# boost.net
KiCad netlist of a schematic drawn in Altium Designer
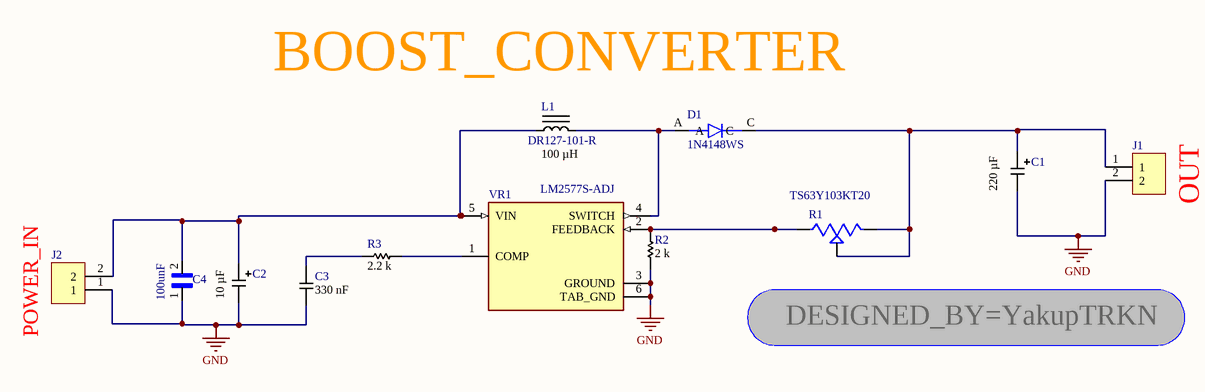
[diagram p0: boost__.SchDoc]

(export (version "E")
  (design (tool "Eeschema 10.0.6"))
  (components
    (comp (ref "C1")
      (value "TAJC227M010RNJ")
      (footprint "KYOCERA_CAP_TAN-C")
      (description "CAP TANT 220UF 20% 10V 2312")
      (fields (field (name "CAPACITANCE") "220 µF"))
      (libsource (lib "boost") (part "TAJC227M010RNJ"))
    )
    (comp (ref "C2")
      (value "T491B106M016AT")
      (footprint "KEMET_CAP_TAN-B")
      (description "CAP TANT 10UF 20% 16V 1411")
      (fields (field (name "CAPACITANCE") "10 µF"))
      (libsource (lib "boost") (part "T491B106M016AT"))
    )
    (comp (ref "C3")
      (value "CL21B334KOCNNNC")
      (footprint "SAMSUNG_CAP_0805_095")
      (description "CAP CER 0.33UF 16V X7R 0805")
      (fields (field (name "CAPACITANCE") "330 nF"))
      (libsource (lib "boost") (part "CL21B334KOCNNNC"))
    )
    (comp (ref "C4")
      (value "100unF")
      (footprint "VJ0603Y104KLXAC5G:CAPC1608X92N")
      (description "Multilayer Ceramic Capacitors MLCC - SMD/SMT 100nF 25volts 10%")
      (fields (field (name "MF") "{'manufacturer': u'Vishay'}") (field (name "MP") "VJ0603Y104KLXAC5G"))
      (libsource (lib "boost") (part "VJ0603Y104KLXAC5G"))
    )
    (comp (ref "D1")
      (value "1N4148WS")
      (footprint "1N4148WS:SODFL2512X100N")
      (description "1N4148WS Series 75 V 300 mA Surface Mount Small Signal Diodes - SOD-323F")
      (fields (field (name "MF") "{'manufacturer': u'ON'}"))
      (libsource (lib "boost") (part "1N4148WS"))
    )
    (comp (ref "J1")
      (value "OUT")
      (footprint "Klemens 1x2 - 3.5mm")
      (description "Klemens 1x2 3.5mm")
      (libsource (lib "boost") (part "Klemens 1x2 3.5mm"))
    )
    (comp (ref "J2")
      (value "POWER_IN")
      (footprint "Klemens 1x2 - 3.5mm")
      (description "Klemens 1x2 3.5mm")
      (libsource (lib "") (part "Klemens 1x2 3.5mm_1"))
    )
    (comp (ref "L1")
      (value "DR127-101-R")
      (footprint "EATON_DR127")
      (description "FIXED IND 100UH 1.96A 163 MOHM")
      (fields (field (name "INDUCTANCE") "100 µH"))
      (libsource (lib "boost") (part "DR127-101-R"))
    )
    (comp (ref "R1")
      (value "TS63Y103KT20")
      (footprint "TS63Y103KT20:TRIM_TS63Y103KT20")
      (fields (field (name "MF") "{'manufacturer': u'Vishay'}"))
      (libsource (lib "boost") (part "TS63Y103KT20"))
    )
    (comp (ref "R2")
      (value "0603SAJ0202T5E")
      (footprint "ROYALOHM_RES_0603")
      (description "RES SMD 2K OHM 5% 1/10W 0603")
      (fields (field (name "RESISTANCE") "2 k"))
      (libsource (lib "boost") (part "0603SAJ0202T5E"))
    )
    (comp (ref "R3")
      (value "0805S8J0222T5E")
      (footprint "ROYALOHM_RES_0805")
      (description "RES SMD 2.2K OHM 5% 1/8W 0805")
      (fields (field (name "RESISTANCE") "2.2 k"))
      (libsource (lib "boost") (part "0805S8J0222T5E"))
    )
    (comp (ref "VR1")
      (value "LM2577S-ADJ")
      (footprint "LM2577S-ADJ:TO170P1524X483-6N")
      (fields (field (name "MF") "{'manufacturer': u'Texas Instruments'}"))
      (libsource (lib "boost") (part "LM2577S-ADJ"))
    )
  )
  (nets
    (net (code "1") (name "GND") (class "Default")
      (node (ref "C1") (pin "2") (pinfunction "2_2") (pintype "passive"))
      (node (ref "C2") (pin "2") (pinfunction "2_2") (pintype "passive"))
      (node (ref "C3") (pin "1") (pinfunction "1_1") (pintype "passive"))
      (node (ref "C4") (pin "1") (pinfunction "1_1") (pintype "passive"))
      (node (ref "J1") (pin "2") (pinfunction "2_2") (pintype "passive"))
      (node (ref "J2") (pin "1") (pinfunction "1_1") (pintype "passive"))
      (node (ref "R2") (pin "2") (pinfunction "2_2") (pintype "passive"))
      (node (ref "VR1") (pin "3") (pinfunction "GROUND_3") (pintype "power_in"))
      (node (ref "VR1") (pin "6") (pinfunction "TAB_GND_6") (pintype "power_in"))
    )
    (net (code "2") (name "Net-(C3-Pad2)") (class "Default")
      (node (ref "C3") (pin "2") (pinfunction "2_2") (pintype "passive"))
      (node (ref "R3") (pin "1") (pinfunction "1_1") (pintype "passive"))
    )
    (net (code "3") (name "Net-(R1-A)") (class "Default")
      (node (ref "R1") (pin "1") (pinfunction "A_1") (pintype "passive"))
      (node (ref "R2") (pin "1") (pinfunction "1_1") (pintype "passive"))
      (node (ref "VR1") (pin "2") (pinfunction "FEEDBACK_2") (pintype "input"))
    )
    (net (code "4") (name "Net-(R1-B)") (class "Default")
      (node (ref "C1") (pin "1") (pinfunction "1_1") (pintype "passive"))
      (node (ref "D1") (pin "C") (pinfunction "C_C") (pintype "passive"))
      (node (ref "J1") (pin "1") (pinfunction "1_1") (pintype "passive"))
      (node (ref "R1") (pin "2") (pinfunction "B_2") (pintype "passive"))
      (node (ref "R1") (pin "3") (pinfunction "C_3") (pintype "passive"))
    )
    (net (code "5") (name "Net-(VR1-COMP)") (class "Default")
      (node (ref "R3") (pin "2") (pinfunction "2_2") (pintype "passive"))
      (node (ref "VR1") (pin "1") (pinfunction "COMP_1") (pintype "passive"))
    )
    (net (code "6") (name "Net-(VR1-SWITCH)") (class "Default")
      (node (ref "D1") (pin "A") (pinfunction "A_A") (pintype "passive"))
      (node (ref "L1") (pin "2") (pinfunction "2_2") (pintype "passive"))
      (node (ref "VR1") (pin "4") (pinfunction "SWITCH_4") (pintype "output"))
    )
    (net (code "7") (name "Net-(VR1-VIN)") (class "Default")
      (node (ref "C2") (pin "1") (pinfunction "1_1") (pintype "passive"))
      (node (ref "C4") (pin "2") (pinfunction "2_2") (pintype "passive"))
      (node (ref "J2") (pin "2") (pinfunction "2_2") (pintype "passive"))
      (node (ref "L1") (pin "1") (pinfunction "1_1") (pintype "passive"))
      (node (ref "VR1") (pin "5") (pinfunction "VIN_5") (pintype "input"))
    )
  )
)
